# DIPESH-1.net
KiCad netlist of a schematic drawn in EAGLE
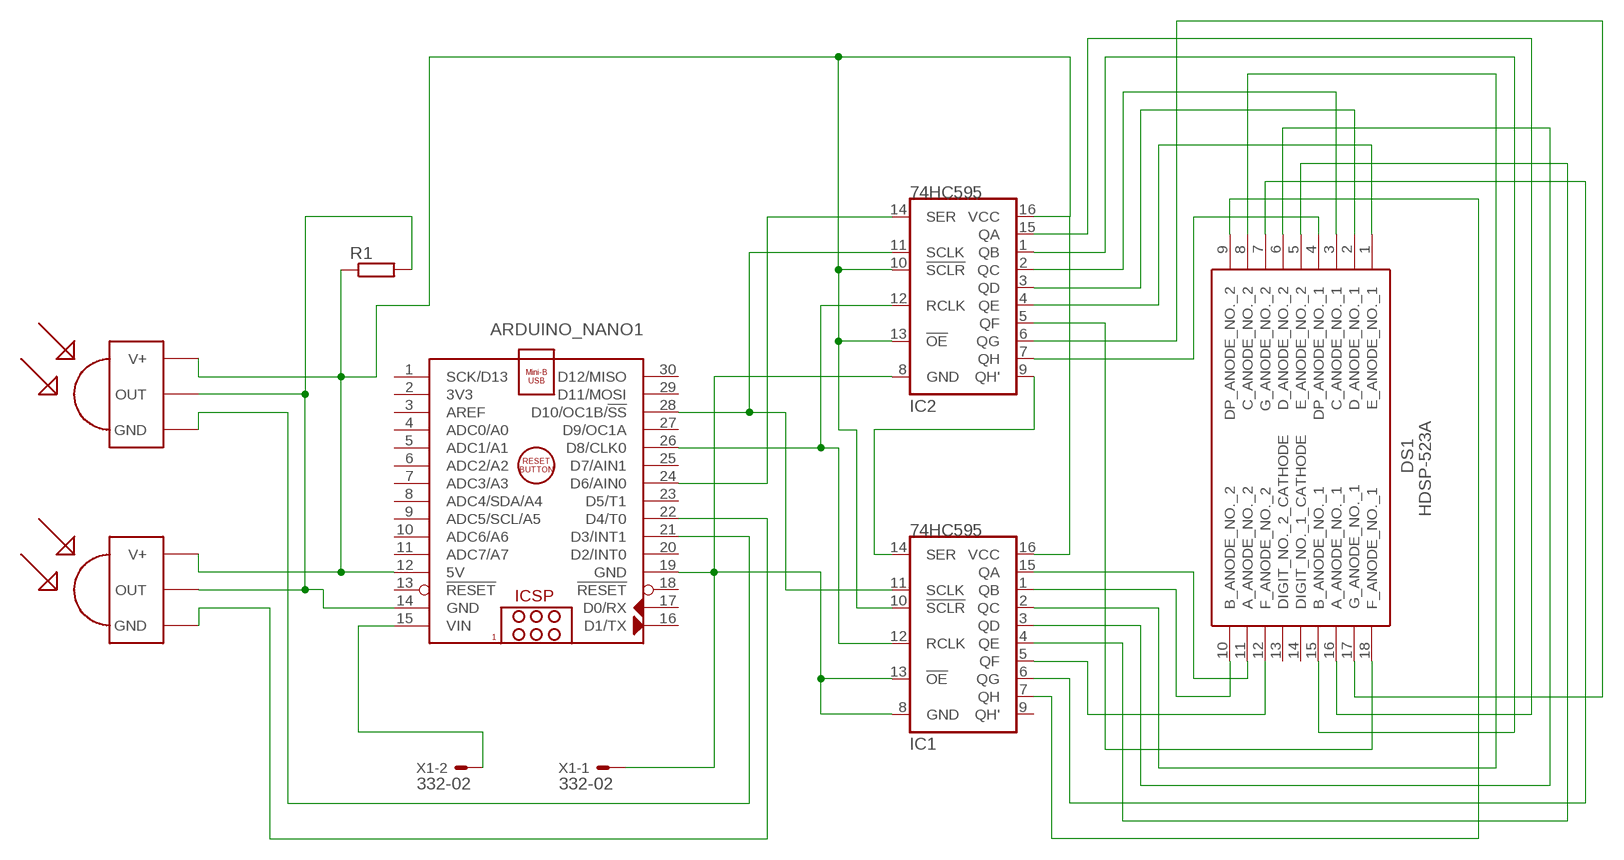
[diagram p0: schematic, sheet 1]

(export (version "E")
  (design (tool "Eeschema 10.0.6"))
  (components
    (comp (ref "ARDUINO_NANO1")
      (value "ARDUINO_NANO")
      (footprint "eagle-import:ARDUINO_NANO")
      (libsource (lib "eagle-import") (part "ARDUINO_NANO"))
    )
    (comp (ref "DS1")
      (value "HDSP-523A")
      (footprint "eagle-import:DIPS1524W50P254L2500H800Q18N")
      (fields (field (name "MOUSER_PART_NUMBER") "630-HDSP-523A"))
      (libsource (lib "eagle-import") (part "HDSP-523A"))
    )
    (comp (ref "IC1")
      (value "74HC595")
      (footprint "eagle-import:SO16")
      (fields (field (name "MF") "Nexperia"))
      (libsource (lib "eagle-import") (part "74HC595"))
    )
    (comp (ref "IC2")
      (value "74HC595")
      (footprint "eagle-import:SO16")
      (fields (field (name "MF") "Nexperia"))
      (libsource (lib "eagle-import") (part "74HC595"))
    )
    (comp (ref "R1")
      (value "R-EU_0207/10")
      (footprint "eagle-import:0207_10")
      (libsource (lib "eagle-import") (part "R-EU_0207/10"))
    )
    (comp (ref "TSOP1")
      (value "TSOP1730")
      (footprint "eagle-import:TSOP17XX")
      (libsource (lib "eagle-import") (part "TSOP1730"))
    )
    (comp (ref "TSOP2")
      (value "TSOP1730")
      (footprint "eagle-import:TSOP17XX")
      (libsource (lib "eagle-import") (part "TSOP1730"))
    )
    (comp (ref "X1")
      (value "332-02")
      (footprint "eagle-import:332-02")
      (libsource (lib "eagle-import") (part "332-02"))
    )
  )
  (nets
    (net (code "1") (name "Net-(ARDUINO_NANO1-5V)") (class "Default")
      (node (ref "ARDUINO_NANO1") (pin "12") (pinfunction "5V_12") (pintype "power_in"))
      (node (ref "IC1") (pin "10") (pinfunction "~{SCLR}_10") (pintype "input"))
      (node (ref "IC1") (pin "16") (pinfunction "VCC_16") (pintype "power_in"))
      (node (ref "IC2") (pin "10") (pinfunction "~{SCLR}_10") (pintype "input"))
      (node (ref "IC2") (pin "13") (pinfunction "~{OE}_13") (pintype "input"))
      (node (ref "IC2") (pin "16") (pinfunction "VCC_16") (pintype "power_in"))
      (node (ref "R1") (pin "1") (pinfunction "1_1") (pintype "passive"))
      (node (ref "TSOP1") (pin "V+") (pinfunction "V+_V+") (pintype "bidirectional"))
      (node (ref "TSOP2") (pin "V+") (pinfunction "V+_V+") (pintype "bidirectional"))
    )
    (net (code "2") (name "Net-(ARDUINO_NANO1-D3{slash}INT1)") (class "Default")
      (node (ref "ARDUINO_NANO1") (pin "21") (pinfunction "D3/INT1_21") (pintype "bidirectional"))
      (node (ref "TSOP1") (pin "GND") (pinfunction "GND_GND") (pintype "bidirectional"))
    )
    (net (code "3") (name "Net-(ARDUINO_NANO1-D4{slash}T0)") (class "Default")
      (node (ref "ARDUINO_NANO1") (pin "22") (pinfunction "D4/T0_22") (pintype "bidirectional"))
      (node (ref "TSOP2") (pin "GND") (pinfunction "GND_GND") (pintype "bidirectional"))
    )
    (net (code "4") (name "Net-(ARDUINO_NANO1-D6{slash}AIN0)") (class "Default")
      (node (ref "ARDUINO_NANO1") (pin "24") (pinfunction "D6/AIN0_24") (pintype "bidirectional"))
      (node (ref "IC2") (pin "14") (pinfunction "SER_14") (pintype "input"))
    )
    (net (code "5") (name "Net-(ARDUINO_NANO1-D8{slash}CLK0)") (class "Default")
      (node (ref "ARDUINO_NANO1") (pin "26") (pinfunction "D8/CLK0_26") (pintype "bidirectional"))
      (node (ref "IC1") (pin "12") (pinfunction "RCLK_12") (pintype "input"))
      (node (ref "IC2") (pin "12") (pinfunction "RCLK_12") (pintype "input"))
    )
    (net (code "6") (name "Net-(ARDUINO_NANO1-D10{slash}OC1B{slash}~{SS})") (class "Default")
      (node (ref "ARDUINO_NANO1") (pin "28") (pinfunction "D10/OC1B/~{SS}_28") (pintype "bidirectional"))
      (node (ref "IC1") (pin "11") (pinfunction "SCLK_11") (pintype "input"))
      (node (ref "IC2") (pin "11") (pinfunction "SCLK_11") (pintype "input"))
    )
    (net (code "7") (name "Net-(ARDUINO_NANO1-GND-Pad14)") (class "Default")
      (node (ref "ARDUINO_NANO1") (pin "14") (pinfunction "GND_14") (pintype "power_in"))
      (node (ref "R1") (pin "2") (pinfunction "2_2") (pintype "passive"))
      (node (ref "TSOP1") (pin "OUT") (pinfunction "OUT_OUT") (pintype "bidirectional"))
      (node (ref "TSOP2") (pin "OUT") (pinfunction "OUT_OUT") (pintype "bidirectional"))
    )
    (net (code "8") (name "Net-(ARDUINO_NANO1-VIN)") (class "Default")
      (node (ref "ARDUINO_NANO1") (pin "15") (pinfunction "VIN_15") (pintype "power_in"))
      (node (ref "X1") (pin "2") (pinfunction "S_2") (pintype "passive"))
    )
    (net (code "9") (name "Net-(DS1-A_ANODE_NO._1)") (class "Default")
      (node (ref "DS1") (pin "16") (pinfunction "A_ANODE_NO._1_16") (pintype "bidirectional"))
      (node (ref "IC2") (pin "15") (pinfunction "QA_15") (pintype "tri_state"))
    )
    (net (code "10") (name "Net-(DS1-A_ANODE_NO._2)") (class "Default")
      (node (ref "DS1") (pin "11") (pinfunction "A_ANODE_NO._2_11") (pintype "bidirectional"))
      (node (ref "IC1") (pin "15") (pinfunction "QA_15") (pintype "tri_state"))
    )
    (net (code "11") (name "Net-(DS1-B_ANODE_NO._1)") (class "Default")
      (node (ref "DS1") (pin "15") (pinfunction "B_ANODE_NO._1_15") (pintype "bidirectional"))
      (node (ref "IC2") (pin "1") (pinfunction "QB_1") (pintype "tri_state"))
    )
    (net (code "12") (name "Net-(DS1-B_ANODE_NO._2)") (class "Default")
      (node (ref "DS1") (pin "10") (pinfunction "B_ANODE_NO._2_10") (pintype "bidirectional"))
      (node (ref "IC1") (pin "1") (pinfunction "QB_1") (pintype "tri_state"))
    )
    (net (code "13") (name "Net-(DS1-C_ANODE_NO._1)") (class "Default")
      (node (ref "DS1") (pin "3") (pinfunction "C_ANODE_NO._1_3") (pintype "bidirectional"))
      (node (ref "IC2") (pin "2") (pinfunction "QC_2") (pintype "tri_state"))
    )
    (net (code "14") (name "Net-(DS1-C_ANODE_NO._2)") (class "Default")
      (node (ref "DS1") (pin "8") (pinfunction "C_ANODE_NO._2_8") (pintype "bidirectional"))
      (node (ref "IC1") (pin "2") (pinfunction "QC_2") (pintype "tri_state"))
    )
    (net (code "15") (name "Net-(DS1-DP_ANODE_NO._1)") (class "Default")
      (node (ref "DS1") (pin "4") (pinfunction "DP_ANODE_NO._1_4") (pintype "bidirectional"))
      (node (ref "IC2") (pin "7") (pinfunction "QH_7") (pintype "tri_state"))
    )
    (net (code "16") (name "Net-(DS1-DP_ANODE_NO._2)") (class "Default")
      (node (ref "DS1") (pin "9") (pinfunction "DP_ANODE_NO._2_9") (pintype "bidirectional"))
      (node (ref "IC1") (pin "7") (pinfunction "QH_7") (pintype "tri_state"))
    )
    (net (code "17") (name "Net-(DS1-D_ANODE_NO._1)") (class "Default")
      (node (ref "DS1") (pin "2") (pinfunction "D_ANODE_NO._1_2") (pintype "bidirectional"))
      (node (ref "IC2") (pin "3") (pinfunction "QD_3") (pintype "tri_state"))
    )
    (net (code "18") (name "Net-(DS1-D_ANODE_NO._2)") (class "Default")
      (node (ref "DS1") (pin "6") (pinfunction "D_ANODE_NO._2_6") (pintype "bidirectional"))
      (node (ref "IC1") (pin "3") (pinfunction "QD_3") (pintype "tri_state"))
    )
    (net (code "19") (name "Net-(DS1-E_ANODE_NO._1)") (class "Default")
      (node (ref "DS1") (pin "1") (pinfunction "E_ANODE_NO._1_1") (pintype "bidirectional"))
      (node (ref "IC2") (pin "4") (pinfunction "QE_4") (pintype "tri_state"))
    )
    (net (code "20") (name "Net-(DS1-E_ANODE_NO._2)") (class "Default")
      (node (ref "DS1") (pin "5") (pinfunction "E_ANODE_NO._2_5") (pintype "bidirectional"))
      (node (ref "IC1") (pin "4") (pinfunction "QE_4") (pintype "tri_state"))
    )
    (net (code "21") (name "Net-(DS1-F_ANODE_NO._1)") (class "Default")
      (node (ref "DS1") (pin "18") (pinfunction "F_ANODE_NO._1_18") (pintype "bidirectional"))
      (node (ref "IC2") (pin "5") (pinfunction "QF_5") (pintype "tri_state"))
    )
    (net (code "22") (name "Net-(DS1-F_ANODE_NO._2)") (class "Default")
      (node (ref "DS1") (pin "12") (pinfunction "F_ANODE_NO._2_12") (pintype "bidirectional"))
      (node (ref "IC1") (pin "5") (pinfunction "QF_5") (pintype "tri_state"))
    )
    (net (code "23") (name "Net-(DS1-G_ANODE_NO._1)") (class "Default")
      (node (ref "DS1") (pin "17") (pinfunction "G_ANODE_NO._1_17") (pintype "bidirectional"))
      (node (ref "IC2") (pin "6") (pinfunction "QG_6") (pintype "tri_state"))
    )
    (net (code "24") (name "Net-(DS1-G_ANODE_NO._2)") (class "Default")
      (node (ref "DS1") (pin "7") (pinfunction "G_ANODE_NO._2_7") (pintype "bidirectional"))
      (node (ref "IC1") (pin "6") (pinfunction "QG_6") (pintype "tri_state"))
    )
    (net (code "25") (name "Net-(IC1-GND)") (class "Default")
      (node (ref "ARDUINO_NANO1") (pin "19") (pinfunction "GND_19") (pintype "power_in"))
      (node (ref "IC1") (pin "13") (pinfunction "~{OE}_13") (pintype "input"))
      (node (ref "IC1") (pin "8") (pinfunction "GND_8") (pintype "power_in"))
      (node (ref "IC2") (pin "8") (pinfunction "GND_8") (pintype "power_in"))
      (node (ref "X1") (pin "1") (pinfunction "S_1") (pintype "passive"))
    )
    (net (code "26") (name "Net-(IC1-SER)") (class "Default")
      (node (ref "IC1") (pin "14") (pinfunction "SER_14") (pintype "input"))
      (node (ref "IC2") (pin "9") (pinfunction "QH'_9") (pintype "tri_state"))
    )
    (net (code "27") (name "unconnected-(ARDUINO_NANO1-3V3-Pad2)") (class "Default")
      (node (ref "ARDUINO_NANO1") (pin "2") (pinfunction "3V3_2") (pintype "output"))
    )
    (net (code "28") (name "unconnected-(ARDUINO_NANO1-ADC0{slash}A0-Pad4)") (class "Default")
      (node (ref "ARDUINO_NANO1") (pin "4") (pinfunction "ADC0/A0_4") (pintype "bidirectional"))
    )
    (net (code "29") (name "unconnected-(ARDUINO_NANO1-ADC1{slash}A1-Pad5)") (class "Default")
      (node (ref "ARDUINO_NANO1") (pin "5") (pinfunction "ADC1/A1_5") (pintype "bidirectional"))
    )
    (net (code "30") (name "unconnected-(ARDUINO_NANO1-ADC2{slash}A2-Pad6)") (class "Default")
      (node (ref "ARDUINO_NANO1") (pin "6") (pinfunction "ADC2/A2_6") (pintype "bidirectional"))
    )
    (net (code "31") (name "unconnected-(ARDUINO_NANO1-ADC3{slash}A3-Pad7)") (class "Default")
      (node (ref "ARDUINO_NANO1") (pin "7") (pinfunction "ADC3/A3_7") (pintype "bidirectional"))
    )
    (net (code "32") (name "unconnected-(ARDUINO_NANO1-ADC4{slash}SDA{slash}A4-Pad8)") (class "Default")
      (node (ref "ARDUINO_NANO1") (pin "8") (pinfunction "ADC4/SDA/A4_8") (pintype "bidirectional"))
    )
    (net (code "33") (name "unconnected-(ARDUINO_NANO1-ADC5{slash}SCL{slash}A5-Pad9)") (class "Default")
      (node (ref "ARDUINO_NANO1") (pin "9") (pinfunction "ADC5/SCL/A5_9") (pintype "bidirectional"))
    )
    (net (code "34") (name "unconnected-(ARDUINO_NANO1-ADC6{slash}A6-Pad10)") (class "Default")
      (node (ref "ARDUINO_NANO1") (pin "10") (pinfunction "ADC6/A6_10") (pintype "bidirectional"))
    )
    (net (code "35") (name "unconnected-(ARDUINO_NANO1-ADC7{slash}A7-Pad11)") (class "Default")
      (node (ref "ARDUINO_NANO1") (pin "11") (pinfunction "ADC7/A7_11") (pintype "bidirectional"))
    )
    (net (code "36") (name "unconnected-(ARDUINO_NANO1-AREF-Pad3)") (class "Default")
      (node (ref "ARDUINO_NANO1") (pin "3") (pinfunction "AREF_3") (pintype "input"))
    )
    (net (code "37") (name "unconnected-(ARDUINO_NANO1-D0{slash}RX-Pad17)") (class "Default")
      (node (ref "ARDUINO_NANO1") (pin "17") (pinfunction "D0/RX_17") (pintype "bidirectional"))
    )
    (net (code "38") (name "unconnected-(ARDUINO_NANO1-D1{slash}TX-Pad16)") (class "Default")
      (node (ref "ARDUINO_NANO1") (pin "16") (pinfunction "D1/TX_16") (pintype "bidirectional"))
    )
    (net (code "39") (name "unconnected-(ARDUINO_NANO1-D2{slash}INT0-Pad20)") (class "Default")
      (node (ref "ARDUINO_NANO1") (pin "20") (pinfunction "D2/INT0_20") (pintype "bidirectional"))
    )
    (net (code "40") (name "unconnected-(ARDUINO_NANO1-D5{slash}T1-Pad23)") (class "Default")
      (node (ref "ARDUINO_NANO1") (pin "23") (pinfunction "D5/T1_23") (pintype "bidirectional"))
    )
    (net (code "41") (name "unconnected-(ARDUINO_NANO1-D7{slash}AIN1-Pad25)") (class "Default")
      (node (ref "ARDUINO_NANO1") (pin "25") (pinfunction "D7/AIN1_25") (pintype "bidirectional"))
    )
    (net (code "42") (name "unconnected-(ARDUINO_NANO1-D9{slash}OC1A-Pad27)") (class "Default")
      (node (ref "ARDUINO_NANO1") (pin "27") (pinfunction "D9/OC1A_27") (pintype "bidirectional"))
    )
    (net (code "43") (name "unconnected-(ARDUINO_NANO1-D11{slash}MOSI-Pad29)") (class "Default")
      (node (ref "ARDUINO_NANO1") (pin "29") (pinfunction "D11/MOSI_29") (pintype "bidirectional"))
    )
    (net (code "44") (name "unconnected-(ARDUINO_NANO1-D12{slash}MISO-Pad30)") (class "Default")
      (node (ref "ARDUINO_NANO1") (pin "30") (pinfunction "D12/MISO_30") (pintype "bidirectional"))
    )
    (net (code "45") (name "unconnected-(ARDUINO_NANO1-SCK{slash}D13-Pad1)") (class "Default")
      (node (ref "ARDUINO_NANO1") (pin "1") (pinfunction "SCK/D13_1") (pintype "bidirectional"))
    )
    (net (code "46") (name "unconnected-(ARDUINO_NANO1-~{RESET}-Pad13)") (class "Default")
      (node (ref "ARDUINO_NANO1") (pin "13") (pinfunction "~{RESET}_13") (pintype "input"))
    )
    (net (code "47") (name "unconnected-(ARDUINO_NANO1-~{RESET}-Pad18)") (class "Default")
      (node (ref "ARDUINO_NANO1") (pin "18") (pinfunction "~{RESET}_18") (pintype "input"))
    )
    (net (code "48") (name "unconnected-(DS1-DIGIT_NO._1_CATHODE-Pad14)") (class "Default")
      (node (ref "DS1") (pin "14") (pinfunction "DIGIT_NO._1_CATHODE_14") (pintype "bidirectional"))
    )
    (net (code "49") (name "unconnected-(DS1-DIGIT_NO._2_CATHODE-Pad13)") (class "Default")
      (node (ref "DS1") (pin "13") (pinfunction "DIGIT_NO._2_CATHODE_13") (pintype "bidirectional"))
    )
    (net (code "50") (name "unconnected-(IC1-QH'-Pad9)") (class "Default")
      (node (ref "IC1") (pin "9") (pinfunction "QH'_9") (pintype "tri_state"))
    )
  )
)
